# Adder.net
KiCad netlist of a schematic drawn in Altium Designer
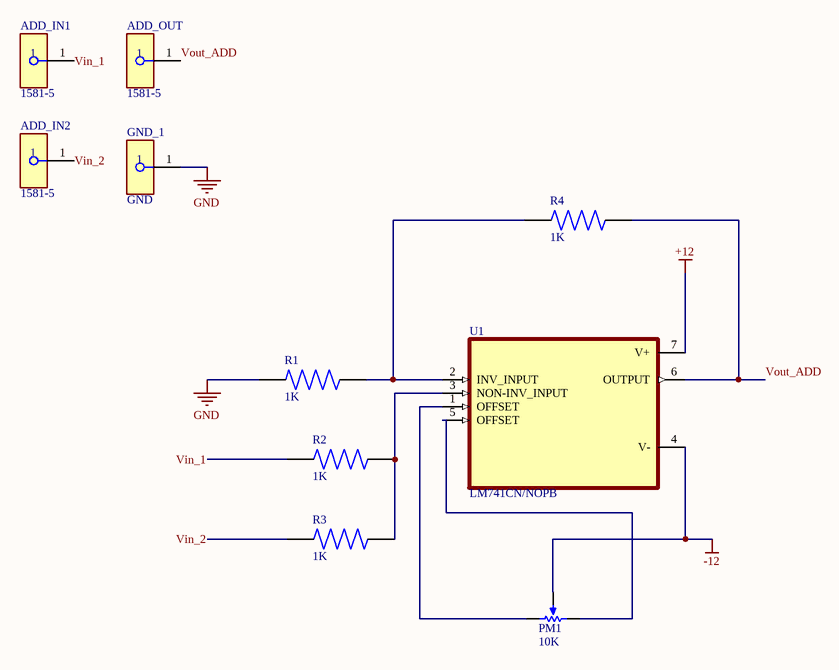
[diagram p0: Adder.SchDoc]

(export (version "E")
  (design (tool "Eeschema 10.0.6"))
  (components
    (comp (ref "ADD_IN1")
      (value "1581-5")
      (footprint "FP-1581-5-MFG")
      (description "CONN BANANA JACK TURRET GREEN")
      (libsource (lib "Altium Content Vault") (part "c5c826e0c4b67fe3b42ef77f2d4decc"))
    )
    (comp (ref "ADD_IN2")
      (value "1581-5")
      (footprint "FP-1581-5-MFG")
      (description "CONN BANANA JACK TURRET GREEN")
      (libsource (lib "Altium Content Vault") (part "c5c826e0c4b67fe3b42ef77f2d4decc"))
    )
    (comp (ref "ADD_OUT")
      (value "1581-5")
      (footprint "FP-1581-5-MFG")
      (description "CONN BANANA JACK TURRET GREEN")
      (libsource (lib "Altium Content Vault") (part "c5c826e0c4b67fe3b42ef77f2d4decc"))
    )
    (comp (ref "GND_1")
      (value "GND")
      (footprint "FP-1581-5-MFG")
      (description "CONN BANANA JACK TURRET GREEN")
      (libsource (lib "Altium Content Vault") (part "c5c826e0c4b67fe3b42ef77f2d4decc"))
    )
    (comp (ref "PM1")
      (value "10K")
      (footprint "PCBComponent_1")
      (libsource (lib "Integrated_Library1") (part "Component_1"))
    )
    (comp (ref "R1")
      (value "1K")
      (footprint "RESAD1100W55L680D260")
      (description "1.07 kOhms Â±1% 0.25W, 1/4W Through Hole Resistor Axial - Metal Film")
      (fields (field (name "MF") "Yageo") (field (name "MP") "MFR-25FBF52-1K"))
      (libsource (lib "MFR-25FBF52-1K") (part "MFR-25FBF52-1K"))
    )
    (comp (ref "R2")
      (value "1K")
      (footprint "RESAD1100W55L680D260")
      (description "1.07 kOhms Â±1% 0.25W, 1/4W Through Hole Resistor Axial - Metal Film")
      (fields (field (name "MF") "Yageo") (field (name "MP") "MFR-25FBF52-1K"))
      (libsource (lib "MFR-25FBF52-1K") (part "MFR-25FBF52-1K"))
    )
    (comp (ref "R3")
      (value "1K")
      (footprint "RESAD1100W55L680D260")
      (description "1.07 kOhms Â±1% 0.25W, 1/4W Through Hole Resistor Axial - Metal Film")
      (fields (field (name "MF") "Yageo") (field (name "MP") "MFR-25FBF52-1K"))
      (libsource (lib "MFR-25FBF52-1K") (part "MFR-25FBF52-1K"))
    )
    (comp (ref "R4")
      (value "1K")
      (footprint "RESAD1100W55L680D260")
      (description "1.07 kOhms Â±1% 0.25W, 1/4W Through Hole Resistor Axial - Metal Film")
      (fields (field (name "MF") "Yageo") (field (name "MP") "MFR-25FBF52-1K"))
      (libsource (lib "MFR-25FBF52-1K") (part "MFR-25FBF52-1K"))
    )
    (comp (ref "U1")
      (value "LM741CN/NOPB")
      (footprint "DIP794W45P254L959H508Q8")
      (description "Single, 44-V, 1-MHz operational amplifier")
      (fields (field (name "MF") "Texas Instruments"))
      (libsource (lib "LM741CN_NOPB (1)") (part "LM741CN/NOPB"))
    )
  )
  (nets
    (net (code "1") (name "+12") (class "Default")
      (node (ref "U1") (pin "7") (pinfunction "V+_7") (pintype "power_in"))
    )
    (net (code "2") (name "-12") (class "Default")
      (node (ref "PM1") (pin "2") (pinfunction "S_2") (pintype "passive"))
      (node (ref "U1") (pin "4") (pinfunction "V-_4") (pintype "power_in"))
    )
    (net (code "3") (name "/Vin_1") (class "Default")
      (node (ref "ADD_IN1") (pin "1") (pinfunction "1_1") (pintype "passive"))
      (node (ref "R2") (pin "1") (pinfunction "1_1") (pintype "passive"))
    )
    (net (code "4") (name "/Vin_2") (class "Default")
      (node (ref "ADD_IN2") (pin "1") (pinfunction "1_1") (pintype "passive"))
      (node (ref "R3") (pin "1") (pinfunction "1_1") (pintype "passive"))
    )
    (net (code "5") (name "/Vout_ADD") (class "Default")
      (node (ref "ADD_OUT") (pin "1") (pinfunction "1_1") (pintype "passive"))
      (node (ref "R4") (pin "2") (pinfunction "2_2") (pintype "passive"))
      (node (ref "U1") (pin "6") (pinfunction "OUTPUT_6") (pintype "output"))
    )
    (net (code "6") (name "GND") (class "Default")
      (node (ref "GND_1") (pin "1") (pinfunction "1_1") (pintype "passive"))
      (node (ref "R1") (pin "1") (pinfunction "1_1") (pintype "passive"))
    )
    (net (code "7") (name "Net-(PM1-CCW)") (class "Default")
      (node (ref "PM1") (pin "1") (pinfunction "CCW_1") (pintype "passive"))
      (node (ref "U1") (pin "5") (pinfunction "OFFSET_5") (pintype "input"))
    )
    (net (code "8") (name "Net-(PM1-CW)") (class "Default")
      (node (ref "PM1") (pin "3") (pinfunction "CW_3") (pintype "passive"))
      (node (ref "U1") (pin "1") (pinfunction "OFFSET_1") (pintype "input"))
    )
    (net (code "9") (name "Net-(U1-INV_INPUT)") (class "Default")
      (node (ref "R1") (pin "2") (pinfunction "2_2") (pintype "passive"))
      (node (ref "R4") (pin "1") (pinfunction "1_1") (pintype "passive"))
      (node (ref "U1") (pin "2") (pinfunction "INV_INPUT_2") (pintype "input"))
    )
    (net (code "10") (name "Net-(U1-NON-INV_INPUT)") (class "Default")
      (node (ref "R2") (pin "2") (pinfunction "2_2") (pintype "passive"))
      (node (ref "R3") (pin "2") (pinfunction "2_2") (pintype "passive"))
      (node (ref "U1") (pin "3") (pinfunction "NON-INV_INPUT_3") (pintype "input"))
    )
  )
)
